# 5_Connectors.net
KiCad netlist of a schematic drawn in Altium Designer
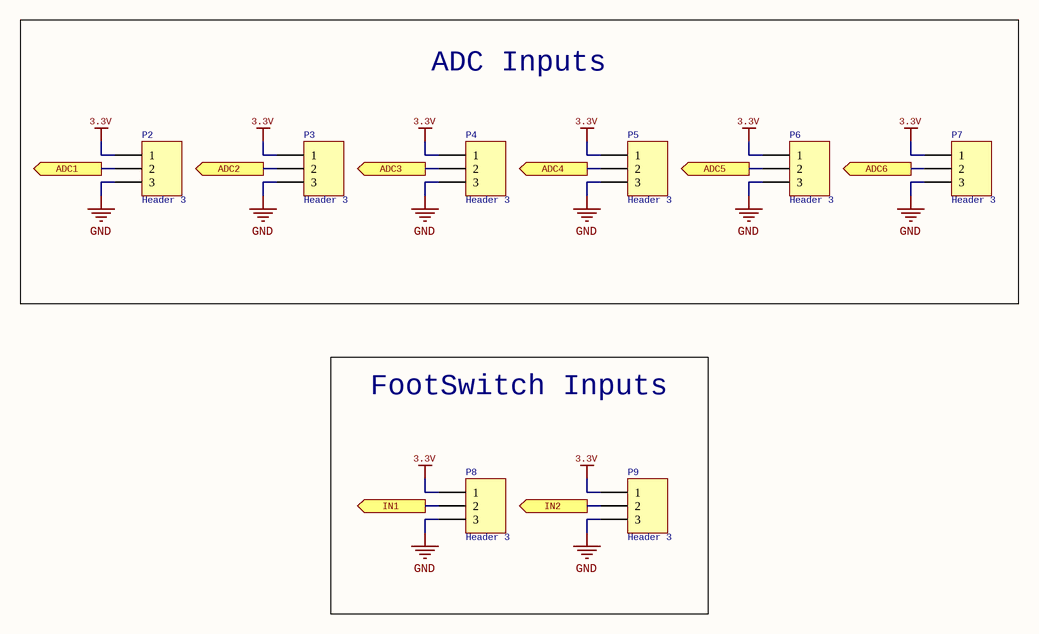
[diagram p0: [5] Connectors.SchDoc]

(export (version "E")
  (design (tool "Eeschema 10.0.6"))
  (components
    (comp (ref "P2")
      (value "Header 3")
      (footprint "HDR1X3")
      (description "Header, 3-Pin")
      (fields (field (name "PUBLISHER") "Altium Limited"))
      (libsource (lib "Miscellaneous Connectors") (part "Header 3"))
    )
    (comp (ref "P3")
      (value "Header 3")
      (footprint "HDR1X3")
      (description "Header, 3-Pin")
      (fields (field (name "PUBLISHER") "Altium Limited"))
      (libsource (lib "Miscellaneous Connectors") (part "Header 3"))
    )
    (comp (ref "P4")
      (value "Header 3")
      (footprint "HDR1X3")
      (description "Header, 3-Pin")
      (fields (field (name "PUBLISHER") "Altium Limited"))
      (libsource (lib "Miscellaneous Connectors") (part "Header 3"))
    )
    (comp (ref "P5")
      (value "Header 3")
      (footprint "HDR1X3")
      (description "Header, 3-Pin")
      (fields (field (name "PUBLISHER") "Altium Limited"))
      (libsource (lib "Miscellaneous Connectors") (part "Header 3"))
    )
    (comp (ref "P6")
      (value "Header 3")
      (footprint "HDR1X3")
      (description "Header, 3-Pin")
      (fields (field (name "PUBLISHER") "Altium Limited"))
      (libsource (lib "Miscellaneous Connectors") (part "Header 3"))
    )
    (comp (ref "P7")
      (value "Header 3")
      (footprint "HDR1X3")
      (description "Header, 3-Pin")
      (fields (field (name "PUBLISHER") "Altium Limited"))
      (libsource (lib "Miscellaneous Connectors") (part "Header 3"))
    )
    (comp (ref "P8")
      (value "Header 3")
      (footprint "HDR1X3")
      (description "Header, 3-Pin")
      (fields (field (name "PUBLISHER") "Altium Limited"))
      (libsource (lib "Miscellaneous Connectors") (part "Header 3"))
    )
    (comp (ref "P9")
      (value "Header 3")
      (footprint "HDR1X3")
      (description "Header, 3-Pin")
      (fields (field (name "PUBLISHER") "Altium Limited"))
      (libsource (lib "Miscellaneous Connectors") (part "Header 3"))
    )
  )
  (nets
    (net (code "1") (name "/ADC1") (class "Default")
      (node (ref "P2") (pin "2") (pinfunction "2_2") (pintype "passive"))
    )
    (net (code "2") (name "/ADC2") (class "Default")
      (node (ref "P3") (pin "2") (pinfunction "2_2") (pintype "passive"))
    )
    (net (code "3") (name "/ADC3") (class "Default")
      (node (ref "P4") (pin "2") (pinfunction "2_2") (pintype "passive"))
    )
    (net (code "4") (name "/ADC4") (class "Default")
      (node (ref "P5") (pin "2") (pinfunction "2_2") (pintype "passive"))
    )
    (net (code "5") (name "/ADC5") (class "Default")
      (node (ref "P6") (pin "2") (pinfunction "2_2") (pintype "passive"))
    )
    (net (code "6") (name "/ADC6") (class "Default")
      (node (ref "P7") (pin "2") (pinfunction "2_2") (pintype "passive"))
    )
    (net (code "7") (name "/IN1") (class "Default")
      (node (ref "P8") (pin "2") (pinfunction "2_2") (pintype "passive"))
    )
    (net (code "8") (name "/IN2") (class "Default")
      (node (ref "P9") (pin "2") (pinfunction "2_2") (pintype "passive"))
    )
    (net (code "9") (name "3.3V") (class "Default")
      (node (ref "P2") (pin "1") (pinfunction "1_1") (pintype "passive"))
      (node (ref "P3") (pin "1") (pinfunction "1_1") (pintype "passive"))
      (node (ref "P4") (pin "1") (pinfunction "1_1") (pintype "passive"))
      (node (ref "P5") (pin "1") (pinfunction "1_1") (pintype "passive"))
      (node (ref "P6") (pin "1") (pinfunction "1_1") (pintype "passive"))
      (node (ref "P7") (pin "1") (pinfunction "1_1") (pintype "passive"))
      (node (ref "P8") (pin "1") (pinfunction "1_1") (pintype "passive"))
      (node (ref "P9") (pin "1") (pinfunction "1_1") (pintype "passive"))
    )
    (net (code "10") (name "GND") (class "Default")
      (node (ref "P2") (pin "3") (pinfunction "3_3") (pintype "passive"))
      (node (ref "P3") (pin "3") (pinfunction "3_3") (pintype "passive"))
      (node (ref "P4") (pin "3") (pinfunction "3_3") (pintype "passive"))
      (node (ref "P5") (pin "3") (pinfunction "3_3") (pintype "passive"))
      (node (ref "P6") (pin "3") (pinfunction "3_3") (pintype "passive"))
      (node (ref "P7") (pin "3") (pinfunction "3_3") (pintype "passive"))
      (node (ref "P8") (pin "3") (pinfunction "3_3") (pintype "passive"))
      (node (ref "P9") (pin "3") (pinfunction "3_3") (pintype "passive"))
    )
  )
)
